# vco_tom.net
KiCad netlist of a schematic drawn in EAGLE
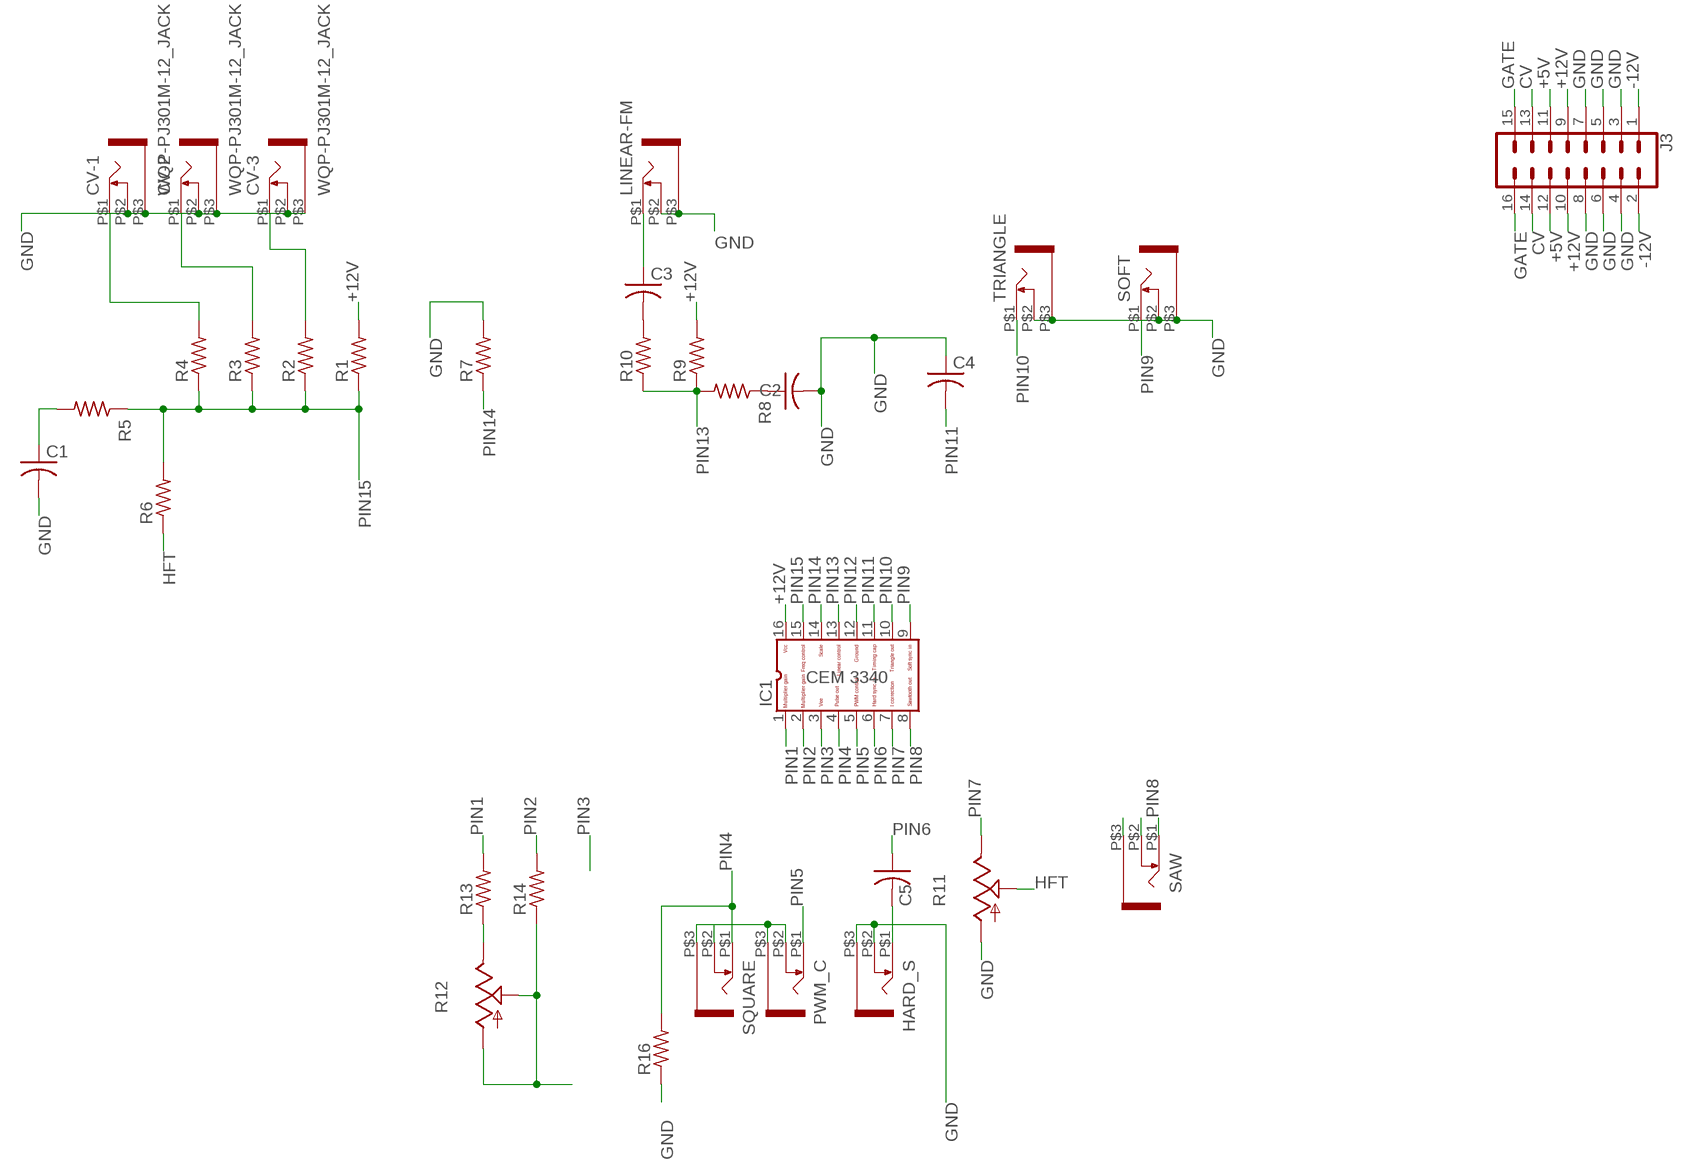
[diagram p0: schematic, sheet 1]

(export (version "E")
  (design (tool "Eeschema 10.0.6"))
  (components
    (comp (ref "C1")
      (value "C-US050-024X044")
      (footprint "eagle-import:C050-024X044")
      (libsource (lib "eagle-import") (part "C-US050-024X044"))
    )
    (comp (ref "C2")
      (value "C-US050-024X044")
      (footprint "eagle-import:C050-024X044")
      (libsource (lib "eagle-import") (part "C-US050-024X044"))
    )
    (comp (ref "C3")
      (value "C-US050-024X044")
      (footprint "eagle-import:C050-024X044")
      (libsource (lib "eagle-import") (part "C-US050-024X044"))
    )
    (comp (ref "C4")
      (value "C-US050-024X044")
      (footprint "eagle-import:C050-024X044")
      (libsource (lib "eagle-import") (part "C-US050-024X044"))
    )
    (comp (ref "C5")
      (value "C-US050-024X044")
      (footprint "eagle-import:C050-024X044")
      (libsource (lib "eagle-import") (part "C-US050-024X044"))
    )
    (comp (ref "CV-1")
      (value "WQP-PJ301M-12_JACK")
      (footprint "eagle-import:WQP-PJ301M-12_JACK")
      (libsource (lib "eagle-import") (part "WQP-PJ301M-12_JACK"))
    )
    (comp (ref "CV-2")
      (value "WQP-PJ301M-12_JACK")
      (footprint "eagle-import:WQP-PJ301M-12_JACK")
      (libsource (lib "eagle-import") (part "WQP-PJ301M-12_JACK"))
    )
    (comp (ref "CV-3")
      (value "WQP-PJ301M-12_JACK")
      (footprint "eagle-import:WQP-PJ301M-12_JACK")
      (libsource (lib "eagle-import") (part "WQP-PJ301M-12_JACK"))
    )
    (comp (ref "HARD_S")
      (value "WQP-PJ301M-12_JACK")
      (footprint "eagle-import:WQP-PJ301M-12_JACK")
      (libsource (lib "eagle-import") (part "WQP-PJ301M-12_JACK"))
    )
    (comp (ref "IC1")
      (value "CEM3340")
      (footprint "eagle-import:DIL16")
      (libsource (lib "eagle-import") (part "CEM3340"))
    )
    (comp (ref "J3")
      (value "CONN_08X2_SHROUD")
      (footprint "eagle-import:2X8-SHROUDED_LOCK")
      (libsource (lib "eagle-import") (part "CONN_08X2_SHROUD"))
    )
    (comp (ref "LINEAR-FM")
      (value "WQP-PJ301M-12_JACK")
      (footprint "eagle-import:WQP-PJ301M-12_JACK")
      (libsource (lib "eagle-import") (part "WQP-PJ301M-12_JACK"))
    )
    (comp (ref "PWM_C")
      (value "WQP-PJ301M-12_JACK")
      (footprint "eagle-import:WQP-PJ301M-12_JACK")
      (libsource (lib "eagle-import") (part "WQP-PJ301M-12_JACK"))
    )
    (comp (ref "R1")
      (value "R-US_0207/10")
      (footprint "eagle-import:0207_10")
      (libsource (lib "eagle-import") (part "R-US_0207/10"))
    )
    (comp (ref "R2")
      (value "R-US_0207/10")
      (footprint "eagle-import:0207_10")
      (libsource (lib "eagle-import") (part "R-US_0207/10"))
    )
    (comp (ref "R3")
      (value "R-US_0207/10")
      (footprint "eagle-import:0207_10")
      (libsource (lib "eagle-import") (part "R-US_0207/10"))
    )
    (comp (ref "R4")
      (value "R-US_0207/10")
      (footprint "eagle-import:0207_10")
      (libsource (lib "eagle-import") (part "R-US_0207/10"))
    )
    (comp (ref "R5")
      (value "R-US_0207/10")
      (footprint "eagle-import:0207_10")
      (libsource (lib "eagle-import") (part "R-US_0207/10"))
    )
    (comp (ref "R6")
      (value "R-US_0207/10")
      (footprint "eagle-import:0207_10")
      (libsource (lib "eagle-import") (part "R-US_0207/10"))
    )
    (comp (ref "R7")
      (value "R-US_0207/10")
      (footprint "eagle-import:0207_10")
      (libsource (lib "eagle-import") (part "R-US_0207/10"))
    )
    (comp (ref "R8")
      (value "R-US_0207/10")
      (footprint "eagle-import:0207_10")
      (libsource (lib "eagle-import") (part "R-US_0207/10"))
    )
    (comp (ref "R9")
      (value "R-US_0207/10")
      (footprint "eagle-import:0207_10")
      (libsource (lib "eagle-import") (part "R-US_0207/10"))
    )
    (comp (ref "R10")
      (value "R-US_0207/10")
      (footprint "eagle-import:0207_10")
      (libsource (lib "eagle-import") (part "R-US_0207/10"))
    )
    (comp (ref "R11")
      (value "TRIM_US-B64Y")
      (footprint "eagle-import:B64Y")
      (libsource (lib "eagle-import") (part "TRIM_US-B64Y"))
    )
    (comp (ref "R12")
      (value "TRIM_US-B64Y")
      (footprint "eagle-import:B64Y")
      (libsource (lib "eagle-import") (part "TRIM_US-B64Y"))
    )
    (comp (ref "R13")
      (value "R-US_0207/10")
      (footprint "eagle-import:0207_10")
      (libsource (lib "eagle-import") (part "R-US_0207/10"))
    )
    (comp (ref "R14")
      (value "R-US_0207/10")
      (footprint "eagle-import:0207_10")
      (libsource (lib "eagle-import") (part "R-US_0207/10"))
    )
    (comp (ref "R16")
      (value "R-US_0207/10")
      (footprint "eagle-import:0207_10")
      (libsource (lib "eagle-import") (part "R-US_0207/10"))
    )
    (comp (ref "SAW")
      (value "WQP-PJ301M-12_JACK")
      (footprint "eagle-import:WQP-PJ301M-12_JACK")
      (libsource (lib "eagle-import") (part "WQP-PJ301M-12_JACK"))
    )
    (comp (ref "SOFT")
      (value "WQP-PJ301M-12_JACK")
      (footprint "eagle-import:WQP-PJ301M-12_JACK")
      (libsource (lib "eagle-import") (part "WQP-PJ301M-12_JACK"))
    )
    (comp (ref "SQUARE")
      (value "WQP-PJ301M-12_JACK")
      (footprint "eagle-import:WQP-PJ301M-12_JACK")
      (libsource (lib "eagle-import") (part "WQP-PJ301M-12_JACK"))
    )
    (comp (ref "TRIANGLE")
      (value "WQP-PJ301M-12_JACK")
      (footprint "eagle-import:WQP-PJ301M-12_JACK")
      (libsource (lib "eagle-import") (part "WQP-PJ301M-12_JACK"))
    )
  )
  (nets
    (net (code "1") (name "/+5V") (class "Default")
      (node (ref "J3") (pin "11") (pinfunction "11_11") (pintype "passive"))
      (node (ref "J3") (pin "12") (pinfunction "12_12") (pintype "passive"))
    )
    (net (code "2") (name "/+12V") (class "Default")
      (node (ref "IC1") (pin "16") (pinfunction "16_16") (pintype "power_in"))
      (node (ref "J3") (pin "10") (pinfunction "10_10") (pintype "passive"))
      (node (ref "J3") (pin "9") (pinfunction "9_9") (pintype "passive"))
      (node (ref "R1") (pin "2") (pinfunction "2_2") (pintype "passive"))
      (node (ref "R9") (pin "2") (pinfunction "2_2") (pintype "passive"))
    )
    (net (code "3") (name "/-12V") (class "Default")
      (node (ref "J3") (pin "1") (pinfunction "1_1") (pintype "passive"))
      (node (ref "J3") (pin "2") (pinfunction "2_2") (pintype "passive"))
    )
    (net (code "4") (name "/CV") (class "Default")
      (node (ref "J3") (pin "13") (pinfunction "13_13") (pintype "passive"))
      (node (ref "J3") (pin "14") (pinfunction "14_14") (pintype "passive"))
    )
    (net (code "5") (name "/GATE") (class "Default")
      (node (ref "J3") (pin "15") (pinfunction "15_15") (pintype "passive"))
      (node (ref "J3") (pin "16") (pinfunction "16_16") (pintype "passive"))
    )
    (net (code "6") (name "/GND") (class "Default")
      (node (ref "C1") (pin "2") (pinfunction "2_2") (pintype "passive"))
      (node (ref "C2") (pin "2") (pinfunction "2_2") (pintype "passive"))
      (node (ref "C4") (pin "1") (pinfunction "1_1") (pintype "passive"))
      (node (ref "CV-1") (pin "P$2") (pinfunction "3_P$2") (pintype "passive"))
      (node (ref "CV-1") (pin "P$3") (pinfunction "1_P$3") (pintype "passive"))
      (node (ref "CV-2") (pin "P$2") (pinfunction "3_P$2") (pintype "passive"))
      (node (ref "CV-2") (pin "P$3") (pinfunction "1_P$3") (pintype "passive"))
      (node (ref "CV-3") (pin "P$2") (pinfunction "3_P$2") (pintype "passive"))
      (node (ref "CV-3") (pin "P$3") (pinfunction "1_P$3") (pintype "passive"))
      (node (ref "HARD_S") (pin "P$2") (pinfunction "3_P$2") (pintype "passive"))
      (node (ref "HARD_S") (pin "P$3") (pinfunction "1_P$3") (pintype "passive"))
      (node (ref "J3") (pin "3") (pinfunction "3_3") (pintype "passive"))
      (node (ref "J3") (pin "4") (pinfunction "4_4") (pintype "passive"))
      (node (ref "J3") (pin "5") (pinfunction "5_5") (pintype "passive"))
      (node (ref "J3") (pin "6") (pinfunction "6_6") (pintype "passive"))
      (node (ref "J3") (pin "7") (pinfunction "7_7") (pintype "passive"))
      (node (ref "J3") (pin "8") (pinfunction "8_8") (pintype "passive"))
      (node (ref "LINEAR-FM") (pin "P$2") (pinfunction "3_P$2") (pintype "passive"))
      (node (ref "LINEAR-FM") (pin "P$3") (pinfunction "1_P$3") (pintype "passive"))
      (node (ref "R11") (pin "A") (pinfunction "A_A") (pintype "passive"))
      (node (ref "R16") (pin "1") (pinfunction "1_1") (pintype "passive"))
      (node (ref "R7") (pin "2") (pinfunction "2_2") (pintype "passive"))
      (node (ref "SOFT") (pin "P$2") (pinfunction "3_P$2") (pintype "passive"))
      (node (ref "SOFT") (pin "P$3") (pinfunction "1_P$3") (pintype "passive"))
      (node (ref "TRIANGLE") (pin "P$2") (pinfunction "3_P$2") (pintype "passive"))
      (node (ref "TRIANGLE") (pin "P$3") (pinfunction "1_P$3") (pintype "passive"))
    )
    (net (code "7") (name "/HFT") (class "Default")
      (node (ref "R11") (pin "S") (pinfunction "S_S") (pintype "passive"))
      (node (ref "R6") (pin "1") (pinfunction "1_1") (pintype "passive"))
    )
    (net (code "8") (name "/PIN1") (class "Default")
      (node (ref "IC1") (pin "1") (pinfunction "1_1") (pintype "bidirectional"))
      (node (ref "R13") (pin "2") (pinfunction "2_2") (pintype "passive"))
    )
    (net (code "9") (name "/PIN2") (class "Default")
      (node (ref "IC1") (pin "2") (pinfunction "2_2") (pintype "bidirectional"))
      (node (ref "R14") (pin "2") (pinfunction "2_2") (pintype "passive"))
    )
    (net (code "10") (name "/PIN3") (class "Default")
      (node (ref "IC1") (pin "3") (pinfunction "3_3") (pintype "power_in"))
    )
    (net (code "11") (name "/PIN4") (class "Default")
      (node (ref "IC1") (pin "4") (pinfunction "4_4") (pintype "output"))
      (node (ref "R16") (pin "2") (pinfunction "2_2") (pintype "passive"))
      (node (ref "SQUARE") (pin "P$1") (pinfunction "2_P$1") (pintype "passive"))
    )
    (net (code "12") (name "/PIN5") (class "Default")
      (node (ref "IC1") (pin "5") (pinfunction "5_5") (pintype "input"))
      (node (ref "PWM_C") (pin "P$1") (pinfunction "2_P$1") (pintype "passive"))
    )
    (net (code "13") (name "/PIN6") (class "Default")
      (node (ref "C5") (pin "1") (pinfunction "1_1") (pintype "passive"))
      (node (ref "IC1") (pin "6") (pinfunction "6_6") (pintype "input"))
    )
    (net (code "14") (name "/PIN7") (class "Default")
      (node (ref "IC1") (pin "7") (pinfunction "7_7") (pintype "bidirectional"))
      (node (ref "R11") (pin "E") (pinfunction "E_E") (pintype "passive"))
    )
    (net (code "15") (name "/PIN8") (class "Default")
      (node (ref "IC1") (pin "8") (pinfunction "8_8") (pintype "output"))
      (node (ref "SAW") (pin "P$1") (pinfunction "2_P$1") (pintype "passive"))
    )
    (net (code "16") (name "/PIN9") (class "Default")
      (node (ref "IC1") (pin "9") (pinfunction "9_9") (pintype "input"))
      (node (ref "SOFT") (pin "P$1") (pinfunction "2_P$1") (pintype "passive"))
    )
    (net (code "17") (name "/PIN10") (class "Default")
      (node (ref "IC1") (pin "10") (pinfunction "10_10") (pintype "output"))
      (node (ref "TRIANGLE") (pin "P$1") (pinfunction "2_P$1") (pintype "passive"))
    )
    (net (code "18") (name "/PIN11") (class "Default")
      (node (ref "C4") (pin "2") (pinfunction "2_2") (pintype "passive"))
      (node (ref "IC1") (pin "11") (pinfunction "11_11") (pintype "bidirectional"))
    )
    (net (code "19") (name "/PIN12") (class "Default")
      (node (ref "IC1") (pin "12") (pinfunction "12_12") (pintype "power_in"))
    )
    (net (code "20") (name "/PIN13") (class "Default")
      (node (ref "IC1") (pin "13") (pinfunction "13_13") (pintype "input"))
      (node (ref "R10") (pin "1") (pinfunction "1_1") (pintype "passive"))
      (node (ref "R8") (pin "2") (pinfunction "2_2") (pintype "passive"))
      (node (ref "R9") (pin "1") (pinfunction "1_1") (pintype "passive"))
    )
    (net (code "21") (name "/PIN14") (class "Default")
      (node (ref "IC1") (pin "14") (pinfunction "14_14") (pintype "input"))
      (node (ref "R7") (pin "1") (pinfunction "1_1") (pintype "passive"))
    )
    (net (code "22") (name "/PIN15") (class "Default")
      (node (ref "IC1") (pin "15") (pinfunction "15_15") (pintype "input"))
      (node (ref "R1") (pin "1") (pinfunction "1_1") (pintype "passive"))
      (node (ref "R2") (pin "1") (pinfunction "1_1") (pintype "passive"))
      (node (ref "R3") (pin "1") (pinfunction "1_1") (pintype "passive"))
      (node (ref "R4") (pin "1") (pinfunction "1_1") (pintype "passive"))
      (node (ref "R5") (pin "1") (pinfunction "1_1") (pintype "passive"))
      (node (ref "R6") (pin "2") (pinfunction "2_2") (pintype "passive"))
    )
    (net (code "23") (name "Net-(C1-Pad1)") (class "Default")
      (node (ref "C1") (pin "1") (pinfunction "1_1") (pintype "passive"))
      (node (ref "R5") (pin "2") (pinfunction "2_2") (pintype "passive"))
    )
    (net (code "24") (name "Net-(C2-Pad1)") (class "Default")
      (node (ref "C2") (pin "1") (pinfunction "1_1") (pintype "passive"))
      (node (ref "R8") (pin "1") (pinfunction "1_1") (pintype "passive"))
    )
    (net (code "25") (name "Net-(C3-Pad2)") (class "Default")
      (node (ref "C3") (pin "2") (pinfunction "2_2") (pintype "passive"))
      (node (ref "R10") (pin "2") (pinfunction "2_2") (pintype "passive"))
    )
    (net (code "26") (name "Net-(CV-1-2)") (class "Default")
      (node (ref "CV-1") (pin "P$1") (pinfunction "2_P$1") (pintype "passive"))
      (node (ref "R4") (pin "2") (pinfunction "2_2") (pintype "passive"))
    )
    (net (code "27") (name "Net-(CV-2-2)") (class "Default")
      (node (ref "CV-2") (pin "P$1") (pinfunction "2_P$1") (pintype "passive"))
      (node (ref "R3") (pin "2") (pinfunction "2_2") (pintype "passive"))
    )
    (net (code "28") (name "Net-(CV-3-2)") (class "Default")
      (node (ref "CV-3") (pin "P$1") (pinfunction "2_P$1") (pintype "passive"))
      (node (ref "R2") (pin "2") (pinfunction "2_2") (pintype "passive"))
    )
    (net (code "29") (name "Net-(HARD_S-2)") (class "Default")
      (node (ref "C5") (pin "2") (pinfunction "2_2") (pintype "passive"))
      (node (ref "HARD_S") (pin "P$1") (pinfunction "2_P$1") (pintype "passive"))
    )
    (net (code "30") (name "Net-(LINEAR-FM-2)") (class "Default")
      (node (ref "C3") (pin "1") (pinfunction "1_1") (pintype "passive"))
      (node (ref "LINEAR-FM") (pin "P$1") (pinfunction "2_P$1") (pintype "passive"))
    )
    (net (code "31") (name "Net-(PWM_C-1)") (class "Default")
      (node (ref "PWM_C") (pin "P$2") (pinfunction "3_P$2") (pintype "passive"))
      (node (ref "PWM_C") (pin "P$3") (pinfunction "1_P$3") (pintype "passive"))
      (node (ref "SQUARE") (pin "P$3") (pinfunction "1_P$3") (pintype "passive"))
    )
    (net (code "32") (name "Net-(R12-PadA)") (class "Default")
      (node (ref "R12") (pin "A") (pinfunction "A_A") (pintype "passive"))
      (node (ref "R12") (pin "S") (pinfunction "S_S") (pintype "passive"))
      (node (ref "R14") (pin "1") (pinfunction "1_1") (pintype "passive"))
    )
    (net (code "33") (name "Net-(R12-PadE)") (class "Default")
      (node (ref "R12") (pin "E") (pinfunction "E_E") (pintype "passive"))
      (node (ref "R13") (pin "1") (pinfunction "1_1") (pintype "passive"))
    )
    (net (code "34") (name "unconnected-(SAW-1-PadP$3)") (class "Default")
      (node (ref "SAW") (pin "P$3") (pinfunction "1_P$3") (pintype "passive"))
    )
    (net (code "35") (name "unconnected-(SAW-3-PadP$2)") (class "Default")
      (node (ref "SAW") (pin "P$2") (pinfunction "3_P$2") (pintype "passive"))
    )
    (net (code "36") (name "unconnected-(SQUARE-3-PadP$2)") (class "Default")
      (node (ref "SQUARE") (pin "P$2") (pinfunction "3_P$2") (pintype "passive"))
    )
  )
)
